# power_battery.net
KiCad netlist of a schematic drawn in Altium Designer
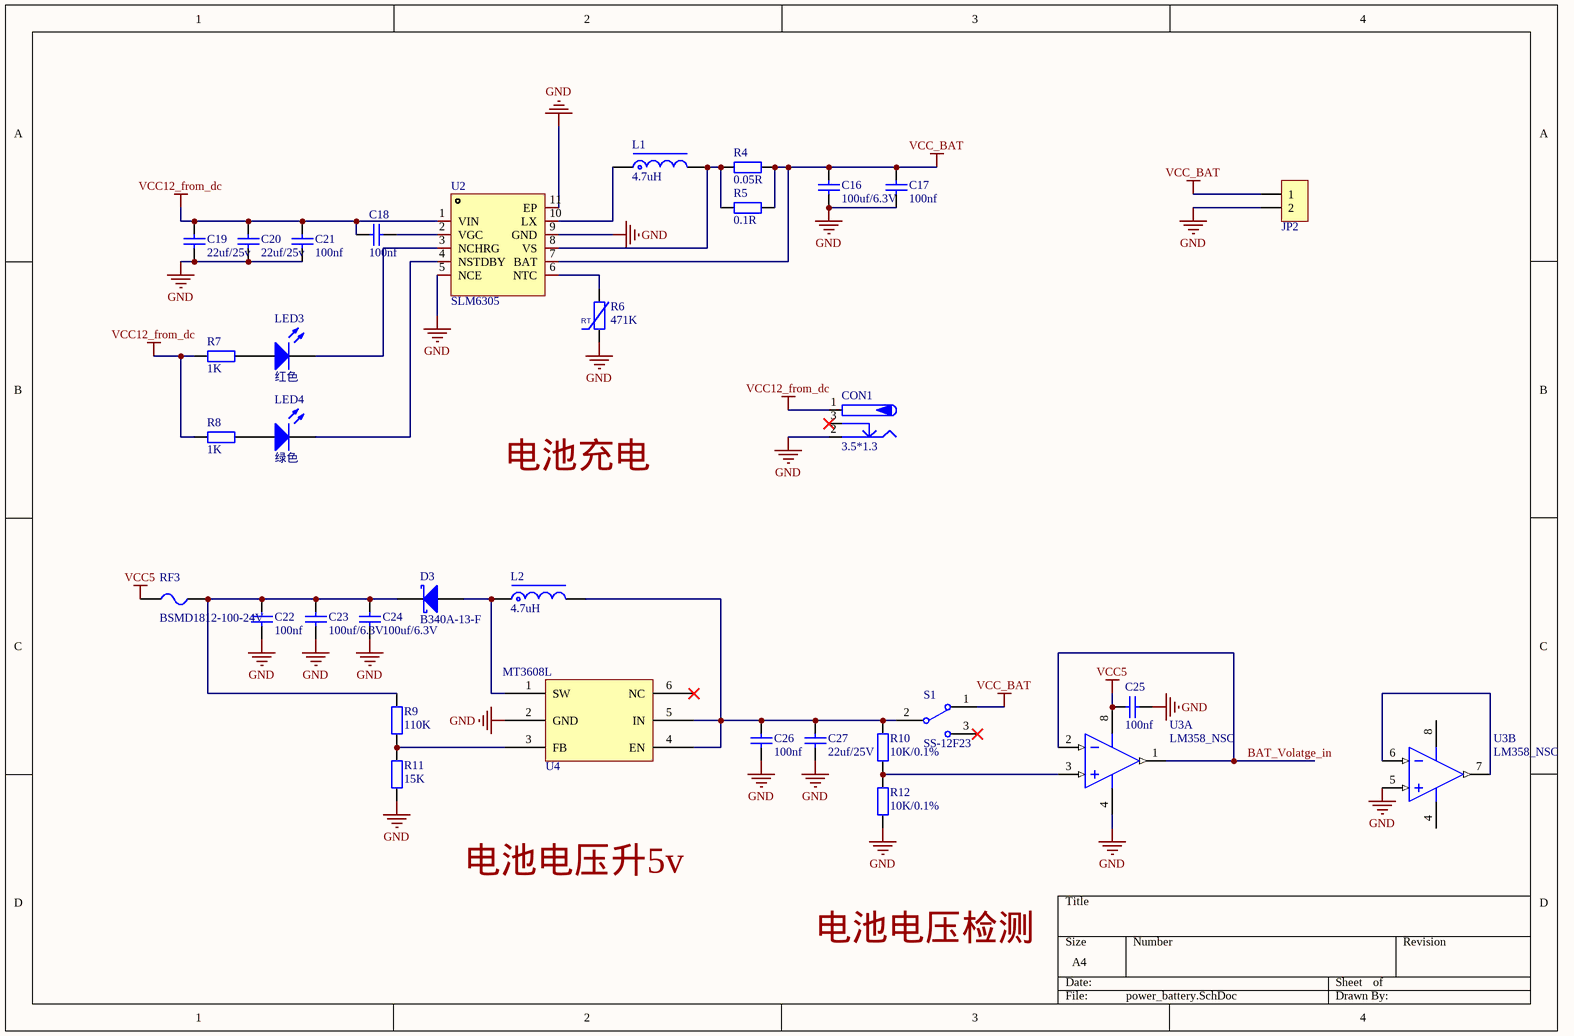
[diagram p0: power_battery.SchDoc]

(export (version "E")
  (design (tool "Eeschema 10.0.6"))
  (components
    (comp (ref "C16")
      (value "100uf/6.3V")
      (footprint "C1206_L")
      (description "贴片电容/MLCC电容")
      (libsource (lib "0.1 - 电阻-电容-电感-保险丝-晶振-晶体-磁珠-电位器-法拉电容-馈通电容") (part "C"))
    )
    (comp (ref "C17")
      (value "100nf")
      (footprint "C0603_L")
      (description "贴片电容/MLCC电容")
      (libsource (lib "0.1 - 电阻-电容-电感-保险丝-晶振-晶体-磁珠-电位器-法拉电容-馈通电容") (part "C"))
    )
    (comp (ref "C18")
      (value "100nf")
      (footprint "C0603_L")
      (description "贴片电容/MLCC电容")
      (libsource (lib "0.1 - 电阻-电容-电感-保险丝-晶振-晶体-磁珠-电位器-法拉电容-馈通电容") (part "C"))
    )
    (comp (ref "C19")
      (value "22uf/25v")
      (footprint "C0805_L")
      (description "贴片电容/MLCC电容")
      (libsource (lib "0.1 - 电阻-电容-电感-保险丝-晶振-晶体-磁珠-电位器-法拉电容-馈通电容") (part "C"))
    )
    (comp (ref "C20")
      (value "22uf/25v")
      (footprint "C0805_L")
      (description "贴片电容/MLCC电容")
      (libsource (lib "0.1 - 电阻-电容-电感-保险丝-晶振-晶体-磁珠-电位器-法拉电容-馈通电容") (part "C"))
    )
    (comp (ref "C21")
      (value "100nf")
      (footprint "C0603_L")
      (description "贴片电容/MLCC电容")
      (libsource (lib "0.1 - 电阻-电容-电感-保险丝-晶振-晶体-磁珠-电位器-法拉电容-馈通电容") (part "C"))
    )
    (comp (ref "C22")
      (value "100nf")
      (footprint "C0603_L")
      (description "贴片电容/MLCC电容")
      (libsource (lib "0.1 - 电阻-电容-电感-保险丝-晶振-晶体-磁珠-电位器-法拉电容-馈通电容") (part "C"))
    )
    (comp (ref "C23")
      (value "100uf/6.3V")
      (footprint "C1206_L")
      (description "贴片电容/MLCC电容")
      (libsource (lib "0.1 - 电阻-电容-电感-保险丝-晶振-晶体-磁珠-电位器-法拉电容-馈通电容") (part "C"))
    )
    (comp (ref "C24")
      (value "100uf/6.3V")
      (footprint "C1206_L")
      (description "贴片电容/MLCC电容")
      (libsource (lib "0.1 - 电阻-电容-电感-保险丝-晶振-晶体-磁珠-电位器-法拉电容-馈通电容") (part "C"))
    )
    (comp (ref "C25")
      (value "100nf")
      (footprint "C0603_L")
      (description "贴片电容/MLCC电容")
      (libsource (lib "0.1 - 电阻-电容-电感-保险丝-晶振-晶体-磁珠-电位器-法拉电容-馈通电容") (part "C"))
    )
    (comp (ref "C26")
      (value "100nf")
      (footprint "C0603_L")
      (description "贴片电容/MLCC电容")
      (libsource (lib "0.1 - 电阻-电容-电感-保险丝-晶振-晶体-磁珠-电位器-法拉电容-馈通电容") (part "C"))
    )
    (comp (ref "C27")
      (value "22uf/25V")
      (footprint "C1206_L")
      (description "贴片电容/MLCC电容")
      (libsource (lib "0.1 - 电阻-电容-电感-保险丝-晶振-晶体-磁珠-电位器-法拉电容-馈通电容") (part "C"))
    )
    (comp (ref "CON1")
      (value "3.5*1.3")
      (footprint "DC-005")
      (description "低压DC电源接口")
      (libsource (lib "0.6 - 电源_音频_USB Type-C_HDMI_XT60_5557_D-SUB_RJ45_SD-TF_SIM插座") (part "DC002~DC005"))
    )
    (comp (ref "D3")
      (value "B340A-13-F")
      (footprint "SMA")
      (description "肖特基二极管 C85098")
      (libsource (lib "HT") (part "B340A-13-F"))
    )
    (comp (ref "JP2")
      (value "HDR-1X2")
      (footprint "PH2.0-L-2P")
      (description "2P接插件")
      (libsource (lib "5.4 - 2.0mm连接器(PHB2.0_PHD2.0_2.0排针排母)") (part "Header 2"))
    )
    (comp (ref "L1")
      (value "4.7uH")
      (footprint "CD53")
      (description "CD系列贴片线绕功率电感")
      (libsource (lib "0.1 - 电阻-电容-电感-保险丝-晶振-晶体-磁珠-电位器-法拉电容-馈通电容") (part "L-SMD"))
    )
    (comp (ref "L2")
      (value "4.7uH")
      (footprint "CD53")
      (description "CD系列贴片线绕功率电感")
      (libsource (lib "0.1 - 电阻-电容-电感-保险丝-晶振-晶体-磁珠-电位器-法拉电容-馈通电容") (part "L-SMD"))
    )
    (comp (ref "LED3")
      (value "红色")
      (footprint "LED0603_Y")
      (description "贴片LED")
      (libsource (lib "0.3 - LED发光二极管-IR二极管_接收管-光耦") (part "LED"))
    )
    (comp (ref "LED4")
      (value "绿色")
      (footprint "LED0603_Y")
      (description "贴片LED")
      (libsource (lib "0.3 - LED发光二极管-IR二极管_接收管-光耦") (part "LED"))
    )
    (comp (ref "R4")
      (value "0.05R")
      (footprint "R0805_M")
      (description "贴片电阻")
      (libsource (lib "0.1 - 电阻-电容-电感-保险丝-晶振-晶体-磁珠-电位器-法拉电容-馈通电容") (part "R"))
    )
    (comp (ref "R5")
      (value "0.1R")
      (footprint "R0805_M")
      (description "贴片电阻")
      (libsource (lib "0.1 - 电阻-电容-电感-保险丝-晶振-晶体-磁珠-电位器-法拉电容-馈通电容") (part "R"))
    )
    (comp (ref "R6")
      (value "471K")
      (footprint "PK0406")
      (description "热敏电阻")
      (libsource (lib "0.1 - 电阻-电容-电感-保险丝-晶振-晶体-磁珠-电位器-法拉电容-馈通电容") (part "RT"))
    )
    (comp (ref "R7")
      (value "1K")
      (footprint "R0603_L")
      (description "贴片电阻")
      (libsource (lib "0.1 - 电阻-电容-电感-保险丝-晶振-晶体-磁珠-电位器-法拉电容-馈通电容") (part "R"))
    )
    (comp (ref "R8")
      (value "1K")
      (footprint "R0603_L")
      (description "贴片电阻")
      (libsource (lib "0.1 - 电阻-电容-电感-保险丝-晶振-晶体-磁珠-电位器-法拉电容-馈通电容") (part "R"))
    )
    (comp (ref "R9")
      (value "110K")
      (footprint "R0603_L")
      (description "贴片电阻")
      (libsource (lib "0.1 - 电阻-电容-电感-保险丝-晶振-晶体-磁珠-电位器-法拉电容-馈通电容") (part "R"))
    )
    (comp (ref "R10")
      (value "10K/0.1%")
      (footprint "R0603_L")
      (description "贴片电阻")
      (libsource (lib "0.1 - 电阻-电容-电感-保险丝-晶振-晶体-磁珠-电位器-法拉电容-馈通电容") (part "R"))
    )
    (comp (ref "R11")
      (value "15K")
      (footprint "R0603_L")
      (description "贴片电阻")
      (libsource (lib "0.1 - 电阻-电容-电感-保险丝-晶振-晶体-磁珠-电位器-法拉电容-馈通电容") (part "R"))
    )
    (comp (ref "R12")
      (value "10K/0.1%")
      (footprint "R0603_L")
      (description "贴片电阻")
      (libsource (lib "0.1 - 电阻-电容-电感-保险丝-晶振-晶体-磁珠-电位器-法拉电容-馈通电容") (part "R"))
    )
    (comp (ref "RF3")
      (value "BSMD1812-100-24V")
      (footprint "F1812")
      (description "PPTC自恢复保险丝 C910830")
      (libsource (lib "0.1 - 电阻-电容-电感-保险丝-晶振-晶体-磁珠-电位器-法拉电容-馈通电容") (part "FUSE-PPTC"))
    )
    (comp (ref "S1")
      (value "SS-12F23")
      (footprint "SS-12D10")
      (description "1路波动开关")
      (libsource (lib "0.5 - 按键_开关_蜂鸣器_电池_测试点_Mark点_铜柱") (part "SSW-1P"))
    )
    (comp (ref "U2")
      (value "SLM6305")
      (footprint "DFN10-L3.0-W3.0-P0.5_EP")
      (description "1锂电池充电ic 2.5a 4.2v 4V~26V输入")
      (fields (field (name "MANUFACTURER") "无锡松朗微"))
      (libsource (lib "HT") (part "SLM6305"))
    )
    (comp (ref "U3")
      (value "LM358_NSC")
      (footprint "SOP8_N")
      (description "Fast Settling Dual Operational Amplifier")
      (libsource (lib "1.5 - 精密运放-比较器") (part "LM358_NSC"))
    )
    (comp (ref "U4")
      (value "MT3608L")
      (footprint "SOT23-6M")
      (description "Boost升压DC-DC芯片 2-28V")
      (libsource (lib "HT") (part "MT3608L"))
    )
  )
  (nets
    (net (code "1") (name "/BAT_Volatge_in") (class "Default")
      (node (ref "U3") (pin "1") (pinfunction "OUT1_1") (pintype "output"))
      (node (ref "U3") (pin "2") (pinfunction "IN1-_2") (pintype "input"))
    )
    (net (code "2") (name "GND") (class "Default")
      (node (ref "C16") (pin "1") (pinfunction "1_1") (pintype "passive"))
      (node (ref "C17") (pin "1") (pinfunction "1_1") (pintype "passive"))
      (node (ref "C19") (pin "1") (pinfunction "1_1") (pintype "passive"))
      (node (ref "C20") (pin "1") (pinfunction "1_1") (pintype "passive"))
      (node (ref "C21") (pin "2") (pinfunction "2_2") (pintype "passive"))
      (node (ref "C22") (pin "1") (pinfunction "1_1") (pintype "passive"))
      (node (ref "C23") (pin "1") (pinfunction "1_1") (pintype "passive"))
      (node (ref "C24") (pin "1") (pinfunction "1_1") (pintype "passive"))
      (node (ref "C25") (pin "1") (pinfunction "1_1") (pintype "passive"))
      (node (ref "C26") (pin "1") (pinfunction "1_1") (pintype "passive"))
      (node (ref "C27") (pin "1") (pinfunction "1_1") (pintype "passive"))
      (node (ref "CON1") (pin "2") (pintype "power_in"))
      (node (ref "JP2") (pin "2") (pinfunction "2_2") (pintype "passive"))
      (node (ref "R11") (pin "1") (pinfunction "1_1") (pintype "passive"))
      (node (ref "R12") (pin "1") (pinfunction "1_1") (pintype "passive"))
      (node (ref "R6") (pin "1") (pinfunction "1_1") (pintype "passive"))
      (node (ref "U2") (pin "11") (pinfunction "EP_11") (pintype "passive"))
      (node (ref "U2") (pin "5") (pinfunction "NCE_5") (pintype "passive"))
      (node (ref "U2") (pin "9") (pinfunction "GND_9") (pintype "passive"))
      (node (ref "U3") (pin "4") (pinfunction "V-_4") (pintype "power_in"))
      (node (ref "U3") (pin "5") (pinfunction "IN2+_5") (pintype "input"))
      (node (ref "U4") (pin "2") (pinfunction "GND_2") (pintype "passive"))
    )
    (net (code "3") (name "Net-(D3-A)") (class "Default")
      (node (ref "D3") (pin "1") (pinfunction "A_1") (pintype "passive"))
      (node (ref "L2") (pin "1") (pinfunction "1_1") (pintype "passive"))
      (node (ref "U4") (pin "1") (pinfunction "SW_1") (pintype "passive"))
    )
    (net (code "4") (name "Net-(D3-K)") (class "Default")
      (node (ref "C22") (pin "2") (pinfunction "2_2") (pintype "passive"))
      (node (ref "C23") (pin "2") (pinfunction "2_2") (pintype "passive"))
      (node (ref "C24") (pin "2") (pinfunction "2_2") (pintype "passive"))
      (node (ref "D3") (pin "2") (pinfunction "K_2") (pintype "passive"))
      (node (ref "R9") (pin "2") (pinfunction "2_2") (pintype "passive"))
      (node (ref "RF3") (pin "1") (pinfunction "1_1") (pintype "passive"))
    )
    (net (code "5") (name "Net-(LED3-A)") (class "Default")
      (node (ref "LED3") (pin "1") (pinfunction "A_1") (pintype "passive"))
      (node (ref "R7") (pin "2") (pinfunction "2_2") (pintype "passive"))
    )
    (net (code "6") (name "Net-(LED3-K)") (class "Default")
      (node (ref "LED3") (pin "2") (pinfunction "K_2") (pintype "passive"))
      (node (ref "U2") (pin "3") (pinfunction "NCHRG_3") (pintype "passive"))
    )
    (net (code "7") (name "Net-(LED4-A)") (class "Default")
      (node (ref "LED4") (pin "1") (pinfunction "A_1") (pintype "passive"))
      (node (ref "R8") (pin "2") (pinfunction "2_2") (pintype "passive"))
    )
    (net (code "8") (name "Net-(LED4-K)") (class "Default")
      (node (ref "LED4") (pin "2") (pinfunction "K_2") (pintype "passive"))
      (node (ref "U2") (pin "4") (pinfunction "NSTDBY_4") (pintype "passive"))
    )
    (net (code "9") (name "Net-(U2-LX)") (class "Default")
      (node (ref "L1") (pin "1") (pinfunction "1_1") (pintype "passive"))
      (node (ref "U2") (pin "10") (pinfunction "LX_10") (pintype "passive"))
    )
    (net (code "10") (name "Net-(U2-NTC)") (class "Default")
      (node (ref "R6") (pin "2") (pinfunction "2_2") (pintype "passive"))
      (node (ref "U2") (pin "6") (pinfunction "NTC_6") (pintype "passive"))
    )
    (net (code "11") (name "Net-(U2-VGC)") (class "Default")
      (node (ref "C18") (pin "1") (pinfunction "1_1") (pintype "passive"))
      (node (ref "U2") (pin "2") (pinfunction "VGC_2") (pintype "passive"))
    )
    (net (code "12") (name "Net-(U2-VS)") (class "Default")
      (node (ref "L1") (pin "2") (pinfunction "2_2") (pintype "passive"))
      (node (ref "R4") (pin "1") (pinfunction "1_1") (pintype "passive"))
      (node (ref "R5") (pin "1") (pinfunction "1_1") (pintype "passive"))
      (node (ref "U2") (pin "8") (pinfunction "VS_8") (pintype "passive"))
    )
    (net (code "13") (name "Net-(U3A-IN1+)") (class "Default")
      (node (ref "R10") (pin "1") (pinfunction "1_1") (pintype "passive"))
      (node (ref "R12") (pin "2") (pinfunction "2_2") (pintype "passive"))
      (node (ref "U3") (pin "3") (pinfunction "IN1+_3") (pintype "input"))
    )
    (net (code "14") (name "Net-(U3B-IN2-)") (class "Default")
      (node (ref "U3") (pin "6") (pinfunction "IN2-_6") (pintype "input"))
      (node (ref "U3") (pin "7") (pinfunction "OUT2_7") (pintype "output"))
    )
    (net (code "15") (name "Net-(U4-EN)") (class "Default")
      (node (ref "C26") (pin "2") (pinfunction "2_2") (pintype "passive"))
      (node (ref "C27") (pin "2") (pinfunction "2_2") (pintype "passive"))
      (node (ref "L2") (pin "2") (pinfunction "2_2") (pintype "passive"))
      (node (ref "R10") (pin "2") (pinfunction "2_2") (pintype "passive"))
      (node (ref "S1") (pin "2") (pinfunction "2_2") (pintype "passive"))
      (node (ref "U4") (pin "4") (pinfunction "EN_4") (pintype "passive"))
      (node (ref "U4") (pin "5") (pinfunction "IN_5") (pintype "passive"))
    )
    (net (code "16") (name "Net-(U4-FB)") (class "Default")
      (node (ref "R11") (pin "2") (pinfunction "2_2") (pintype "passive"))
      (node (ref "R9") (pin "1") (pinfunction "1_1") (pintype "passive"))
      (node (ref "U4") (pin "3") (pinfunction "FB_3") (pintype "passive"))
    )
    (net (code "17") (name "VCC5") (class "Default")
      (node (ref "C25") (pin "2") (pinfunction "2_2") (pintype "passive"))
      (node (ref "RF3") (pin "2") (pinfunction "2_2") (pintype "passive"))
      (node (ref "U3") (pin "8") (pinfunction "V+_8") (pintype "power_in"))
    )
    (net (code "18") (name "VCC12_from_dc") (class "Default")
      (node (ref "C18") (pin "2") (pinfunction "2_2") (pintype "passive"))
      (node (ref "C19") (pin "2") (pinfunction "2_2") (pintype "passive"))
      (node (ref "C20") (pin "2") (pinfunction "2_2") (pintype "passive"))
      (node (ref "C21") (pin "1") (pinfunction "1_1") (pintype "passive"))
      (node (ref "CON1") (pin "1") (pintype "power_in"))
      (node (ref "R7") (pin "1") (pinfunction "1_1") (pintype "passive"))
      (node (ref "R8") (pin "1") (pinfunction "1_1") (pintype "passive"))
      (node (ref "U2") (pin "1") (pinfunction "VIN_1") (pintype "passive"))
    )
    (net (code "19") (name "VCC_BAT") (class "Default")
      (node (ref "C16") (pin "2") (pinfunction "2_2") (pintype "passive"))
      (node (ref "C17") (pin "2") (pinfunction "2_2") (pintype "passive"))
      (node (ref "JP2") (pin "1") (pinfunction "1_1") (pintype "passive"))
      (node (ref "R4") (pin "2") (pinfunction "2_2") (pintype "passive"))
      (node (ref "R5") (pin "2") (pinfunction "2_2") (pintype "passive"))
      (node (ref "S1") (pin "1") (pinfunction "1_1") (pintype "passive"))
      (node (ref "U2") (pin "7") (pinfunction "BAT_7") (pintype "passive"))
    )
    (net (code "20") (name "unconnected-(CON1-Pad3)") (class "Default")
      (node (ref "CON1") (pin "3") (pintype "power_in+no_connect"))
    )
    (net (code "21") (name "unconnected-(S1-Pad3)") (class "Default")
      (node (ref "S1") (pin "3") (pinfunction "3_3") (pintype "passive+no_connect"))
    )
    (net (code "22") (name "unconnected-(U3B-V+-Pad8)") (class "Default")
      (node (ref "U3") (pin "8") (pinfunction "V+_8") (pintype "power_in"))
    )
    (net (code "23") (name "unconnected-(U3B-V--Pad4)") (class "Default")
      (node (ref "U3") (pin "4") (pinfunction "V-_4") (pintype "power_in"))
    )
    (net (code "24") (name "unconnected-(U4-NC-Pad6)") (class "Default")
      (node (ref "U4") (pin "6") (pinfunction "NC_6") (pintype "passive+no_connect"))
    )
  )
)
